# Lilypad_Schematic_1.net
KiCad netlist of a schematic drawn in Altium Designer
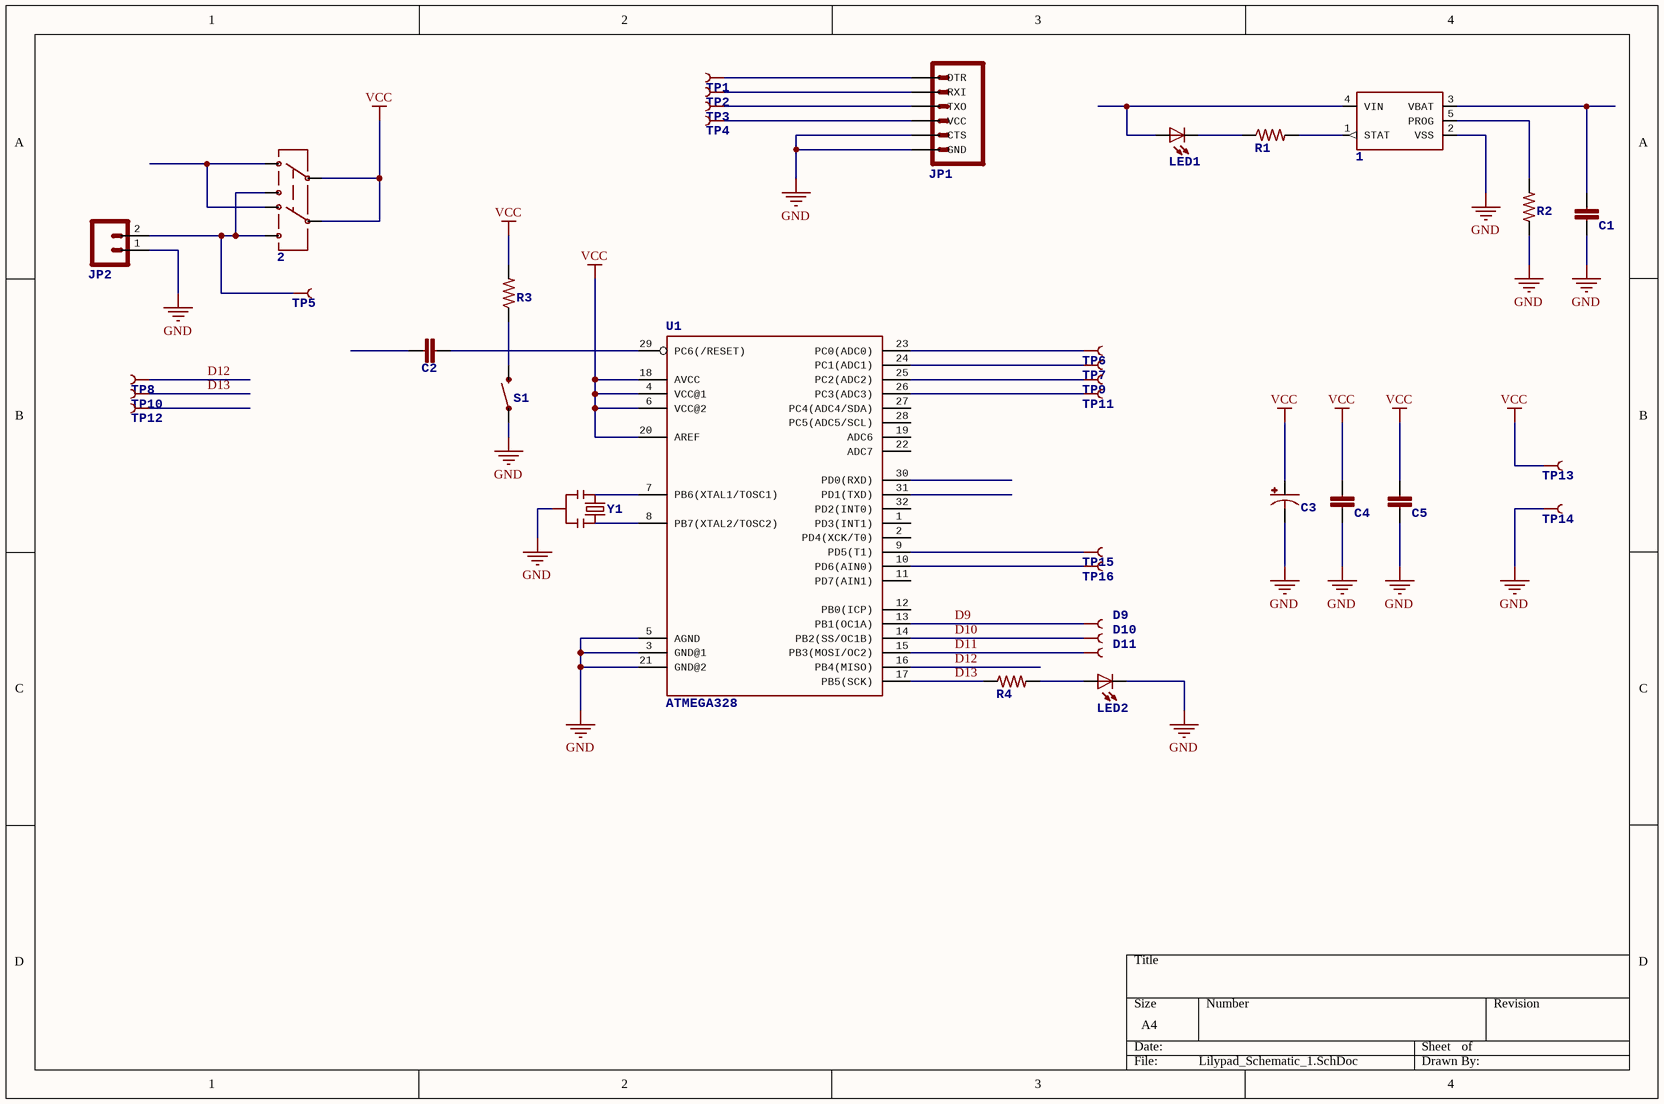
[diagram p0: Lilypad_Schematic_1.SchDoc]

(export (version "E")
  (design (tool "Eeschema 10.0.6"))
  (components
    (comp (ref "1")
      (value "MCP73831")
      (footprint "SOT23-5")
      (libsource (lib "LilyPad Simple v2") (part "MCP73831"))
    )
    (comp (ref "2")
      (value "AYZ0202")
      (footprint "AYZ0202")
      (libsource (lib "LilyPad Simple v2") (part "AYZ0202"))
    )
    (comp (ref "C1") (value "CAP0402-CAP") (footprint "0402-CAP") (libsource (lib "") (part "CAP0402-CAP_1")))
    (comp (ref "C2")
      (value "CAP0402-CAP")
      (footprint "0402-CAP")
      (libsource (lib "LilyPad Simple v2") (part "CAP0402-CAP"))
    )
    (comp (ref "C3")
      (value "CAP_POL3528")
      (footprint "EIA3528")
      (libsource (lib "LilyPad Simple v2") (part "CAP_POL3528"))
    )
    (comp (ref "C4") (value "CAP0402-CAP") (footprint "0402-CAP") (libsource (lib "") (part "CAP0402-CAP_1")))
    (comp (ref "C5") (value "CAP0402-CAP") (footprint "0402-CAP") (libsource (lib "") (part "CAP0402-CAP_1")))
    (comp (ref "D9")
      (value "CONN")
      (footprint "PETAL-LONG-2")
      (libsource (lib "LilyPad Simple v2") (part "CONN"))
    )
    (comp (ref "D10")
      (value "CONN")
      (footprint "PETAL-LONG-2")
      (libsource (lib "LilyPad Simple v2") (part "CONN"))
    )
    (comp (ref "D11")
      (value "CONN")
      (footprint "PETAL-LONG-2")
      (libsource (lib "LilyPad Simple v2") (part "CONN"))
    )
    (comp (ref "JP1")
      (value "ARDUINO_SERIAL_PROGRAMSMD")
      (footprint "1X06-SMD")
      (libsource (lib "LilyPad Simple v2") (part "ARDUINO_SERIAL_PROGRAMSMD"))
    )
    (comp (ref "JP2")
      (value "M02-JST-2MM-SMT")
      (footprint "JST-2-SMD")
      (libsource (lib "LilyPad Simple v2") (part "M02-JST-2MM-SMT"))
    )
    (comp (ref "LED1")
      (value "LED0603")
      (footprint "LED-0603")
      (libsource (lib "LilyPad Simple v2") (part "LED0603"))
    )
    (comp (ref "LED2")
      (value "LED0603")
      (footprint "LED-0603")
      (libsource (lib "LilyPad Simple v2") (part "LED0603"))
    )
    (comp (ref "R1")
      (value "RESISTOR0402-RES")
      (footprint "0402-RES")
      (libsource (lib "LilyPad Simple v2") (part "RESISTOR0402-RES"))
    )
    (comp (ref "R2")
      (value "RESISTOR0402-RES")
      (footprint "0402-RES")
      (libsource (lib "LilyPad Simple v2") (part "RESISTOR0402-RES"))
    )
    (comp (ref "R3")
      (value "RESISTOR0402-RES")
      (footprint "0402-RES")
      (libsource (lib "LilyPad Simple v2") (part "RESISTOR0402-RES"))
    )
    (comp (ref "R4")
      (value "RESISTOR0402-RES")
      (footprint "0402-RES")
      (libsource (lib "LilyPad Simple v2") (part "RESISTOR0402-RES"))
    )
    (comp (ref "S1")
      (value "SWITCH-MOMENTARY-2SMD-2")
      (footprint "TACTILE_SWITCH_SMD-2")
      (libsource (lib "LilyPad Simple v2") (part "SWITCH-MOMENTARY-2SMD-2"))
    )
    (comp (ref "TP1")
      (value "TEST-POINT3X5")
      (footprint "PAD.03X.05")
      (libsource (lib "LilyPad Simple v2") (part "TEST-POINT3X5"))
    )
    (comp (ref "TP2")
      (value "TEST-POINT3X5")
      (footprint "PAD.03X.05")
      (libsource (lib "LilyPad Simple v2") (part "TEST-POINT3X5"))
    )
    (comp (ref "TP3")
      (value "TEST-POINT3X5")
      (footprint "PAD.03X.05")
      (libsource (lib "LilyPad Simple v2") (part "TEST-POINT3X5"))
    )
    (comp (ref "TP4")
      (value "TEST-POINT3X5")
      (footprint "PAD.03X.05")
      (libsource (lib "LilyPad Simple v2") (part "TEST-POINT3X5"))
    )
    (comp (ref "TP5")
      (value "TEST-POINT3X5")
      (footprint "PAD.03X.05")
      (libsource (lib "LilyPad Simple v2") (part "TEST-POINT3X5"))
    )
    (comp (ref "TP6")
      (value "CONN")
      (footprint "PETAL-LONG-2")
      (libsource (lib "LilyPad Simple v2") (part "CONN"))
    )
    (comp (ref "TP7")
      (value "CONN")
      (footprint "PETAL-LONG-2")
      (libsource (lib "LilyPad Simple v2") (part "CONN"))
    )
    (comp (ref "TP8")
      (value "TEST-POINT3X5")
      (footprint "PAD.03X.05")
      (libsource (lib "LilyPad Simple v2") (part "TEST-POINT3X5"))
    )
    (comp (ref "TP9")
      (value "CONN")
      (footprint "PETAL-LONG-2")
      (libsource (lib "LilyPad Simple v2") (part "CONN"))
    )
    (comp (ref "TP10")
      (value "TEST-POINT3X5")
      (footprint "PAD.03X.05")
      (libsource (lib "LilyPad Simple v2") (part "TEST-POINT3X5"))
    )
    (comp (ref "TP11")
      (value "CONN")
      (footprint "PETAL-LONG-2")
      (libsource (lib "LilyPad Simple v2") (part "CONN"))
    )
    (comp (ref "TP12")
      (value "TEST-POINT3X5")
      (footprint "PAD.03X.05")
      (libsource (lib "LilyPad Simple v2") (part "TEST-POINT3X5"))
    )
    (comp (ref "TP13")
      (value "CONN")
      (footprint "PETAL-LONG-2")
      (libsource (lib "LilyPad Simple v2") (part "CONN"))
    )
    (comp (ref "TP14")
      (value "CONN")
      (footprint "PETAL-LONG-2")
      (libsource (lib "LilyPad Simple v2") (part "CONN"))
    )
    (comp (ref "TP15")
      (value "CONN")
      (footprint "PETAL-LONG-2")
      (libsource (lib "LilyPad Simple v2") (part "CONN"))
    )
    (comp (ref "TP16")
      (value "CONN")
      (footprint "PETAL-LONG-2")
      (libsource (lib "LilyPad Simple v2") (part "CONN"))
    )
    (comp (ref "U1")
      (value "ATMEGA328")
      (footprint "TQFP32-08")
      (libsource (lib "LilyPad Simple v2") (part "ATMEGA328"))
    )
    (comp (ref "Y1")
      (value "RESONATORSMD")
      (footprint "RESONATOR-SMD")
      (libsource (lib "LilyPad Simple v2") (part "RESONATORSMD"))
    )
  )
  (nets
    (net (code "1") (name "/D9") (class "Default")
      (node (ref "D9") (pin "1") (pinfunction "1_1") (pintype "passive"))
      (node (ref "U1") (pin "13") (pinfunction "PB1(OC1A)_13") (pintype "passive"))
    )
    (net (code "2") (name "/D10") (class "Default")
      (node (ref "D10") (pin "1") (pinfunction "1_1") (pintype "passive"))
      (node (ref "U1") (pin "14") (pinfunction "PB2(SS/OC1B)_14") (pintype "passive"))
    )
    (net (code "3") (name "/D11") (class "Default")
      (node (ref "D11") (pin "1") (pinfunction "1_1") (pintype "passive"))
      (node (ref "U1") (pin "15") (pinfunction "PB3(MOSI/OC2)_15") (pintype "passive"))
    )
    (net (code "4") (name "/D12") (class "Default")
      (node (ref "TP8") (pin "P$1") (pinfunction "1_P$1") (pintype "passive"))
      (node (ref "U1") (pin "16") (pinfunction "PB4(MISO)_16") (pintype "passive"))
    )
    (net (code "5") (name "/D13") (class "Default")
      (node (ref "R4") (pin "1") (pinfunction "1_1") (pintype "passive"))
      (node (ref "TP10") (pin "P$1") (pinfunction "1_P$1") (pintype "passive"))
      (node (ref "U1") (pin "17") (pinfunction "PB5(SCK)_17") (pintype "passive"))
    )
    (net (code "6") (name "GND") (class "Default")
      (node (ref "1") (pin "2") (pinfunction "VSS_2") (pintype "power_in"))
      (node (ref "C1") (pin "2") (pinfunction "2_2") (pintype "passive"))
      (node (ref "C3") (pin "C") (pinfunction "-_C") (pintype "passive"))
      (node (ref "C4") (pin "2") (pinfunction "2_2") (pintype "passive"))
      (node (ref "C5") (pin "2") (pinfunction "2_2") (pintype "passive"))
      (node (ref "JP1") (pin "5") (pinfunction "CTS_5") (pintype "passive"))
      (node (ref "JP1") (pin "6") (pinfunction "GND_6") (pintype "passive"))
      (node (ref "JP2") (pin "1") (pinfunction "1_1") (pintype "passive"))
      (node (ref "LED2") (pin "C") (pinfunction "C_C") (pintype "passive"))
      (node (ref "R2") (pin "1") (pinfunction "1_1") (pintype "passive"))
      (node (ref "S1") (pin "2") (pinfunction "1_2") (pintype "passive"))
      (node (ref "TP14") (pin "1") (pinfunction "1_1") (pintype "passive"))
      (node (ref "U1") (pin "21") (pinfunction "GND@2_21") (pintype "passive"))
      (node (ref "U1") (pin "3") (pinfunction "GND@1_3") (pintype "passive"))
      (node (ref "U1") (pin "5") (pinfunction "AGND_5") (pintype "passive"))
      (node (ref "Y1") (pin "2") (pinfunction "2_2") (pintype "passive"))
    )
    (net (code "7") (name "Net-(1-PROG)") (class "Default")
      (node (ref "1") (pin "5") (pinfunction "PROG_5") (pintype "passive"))
      (node (ref "R2") (pin "2") (pinfunction "2_2") (pintype "passive"))
    )
    (net (code "8") (name "Net-(1-STAT)") (class "Default")
      (node (ref "1") (pin "1") (pinfunction "STAT_1") (pintype "output"))
      (node (ref "R1") (pin "2") (pinfunction "2_2") (pintype "passive"))
    )
    (net (code "9") (name "Net-(1-VBAT)") (class "Default")
      (node (ref "1") (pin "3") (pinfunction "VBAT_3") (pintype "power_in"))
      (node (ref "C1") (pin "1") (pinfunction "1_1") (pintype "passive"))
    )
    (net (code "10") (name "Net-(1-VIN)") (class "Default")
      (node (ref "1") (pin "4") (pinfunction "VIN_4") (pintype "power_in"))
      (node (ref "LED1") (pin "A") (pinfunction "A_A") (pintype "passive"))
    )
    (net (code "11") (name "Net-(2-1)") (class "Default")
      (node (ref "2") (pin "3") (pinfunction "1_3") (pintype "passive"))
      (node (ref "2") (pin "6") (pinfunction "4_6") (pintype "passive"))
    )
    (net (code "12") (name "Net-(2-3)") (class "Default")
      (node (ref "2") (pin "1") (pinfunction "3_1") (pintype "passive"))
      (node (ref "2") (pin "4") (pinfunction "6_4") (pintype "passive"))
      (node (ref "JP2") (pin "2") (pinfunction "2_2") (pintype "passive"))
      (node (ref "TP5") (pin "P$1") (pinfunction "1_P$1") (pintype "passive"))
    )
    (net (code "13") (name "Net-(JP1-DTR)") (class "Default")
      (node (ref "JP1") (pin "1") (pinfunction "DTR_1") (pintype "passive"))
      (node (ref "TP1") (pin "P$1") (pinfunction "1_P$1") (pintype "passive"))
    )
    (net (code "14") (name "Net-(JP1-RXI)") (class "Default")
      (node (ref "JP1") (pin "2") (pinfunction "RXI_2") (pintype "passive"))
      (node (ref "TP2") (pin "P$1") (pinfunction "1_P$1") (pintype "passive"))
    )
    (net (code "15") (name "Net-(JP1-TXO)") (class "Default")
      (node (ref "JP1") (pin "3") (pinfunction "TXO_3") (pintype "passive"))
      (node (ref "TP3") (pin "P$1") (pinfunction "1_P$1") (pintype "passive"))
    )
    (net (code "16") (name "Net-(JP1-VCC)") (class "Default")
      (node (ref "JP1") (pin "4") (pinfunction "VCC_4") (pintype "passive"))
      (node (ref "TP4") (pin "P$1") (pinfunction "1_P$1") (pintype "passive"))
    )
    (net (code "17") (name "Net-(LED1-PadC)") (class "Default")
      (node (ref "LED1") (pin "C") (pinfunction "C_C") (pintype "passive"))
      (node (ref "R1") (pin "1") (pinfunction "1_1") (pintype "passive"))
    )
    (net (code "18") (name "Net-(LED2-PadA)") (class "Default")
      (node (ref "LED2") (pin "A") (pinfunction "A_A") (pintype "passive"))
      (node (ref "R4") (pin "2") (pinfunction "2_2") (pintype "passive"))
    )
    (net (code "19") (name "Net-(S1-2)") (class "Default")
      (node (ref "R3") (pin "1") (pinfunction "1_1") (pintype "passive"))
      (node (ref "S1") (pin "1") (pinfunction "2_1") (pintype "passive"))
    )
    (net (code "20") (name "Net-(U1-PB6(XTAL1{slash}TOSC1))") (class "Default")
      (node (ref "U1") (pin "7") (pinfunction "PB6(XTAL1/TOSC1)_7") (pintype "passive"))
      (node (ref "Y1") (pin "1") (pinfunction "1_1") (pintype "passive"))
    )
    (net (code "21") (name "Net-(U1-PB7(XTAL2{slash}TOSC2))") (class "Default")
      (node (ref "U1") (pin "8") (pinfunction "PB7(XTAL2/TOSC2)_8") (pintype "passive"))
      (node (ref "Y1") (pin "3") (pinfunction "3_3") (pintype "passive"))
    )
    (net (code "22") (name "Net-(U1-PC0(ADC0))") (class "Default")
      (node (ref "TP6") (pin "1") (pinfunction "1_1") (pintype "passive"))
      (node (ref "U1") (pin "23") (pinfunction "PC0(ADC0)_23") (pintype "passive"))
    )
    (net (code "23") (name "Net-(U1-PC1(ADC1))") (class "Default")
      (node (ref "TP7") (pin "1") (pinfunction "1_1") (pintype "passive"))
      (node (ref "U1") (pin "24") (pinfunction "PC1(ADC1)_24") (pintype "passive"))
    )
    (net (code "24") (name "Net-(U1-PC2(ADC2))") (class "Default")
      (node (ref "TP9") (pin "1") (pinfunction "1_1") (pintype "passive"))
      (node (ref "U1") (pin "25") (pinfunction "PC2(ADC2)_25") (pintype "passive"))
    )
    (net (code "25") (name "Net-(U1-PC3(ADC3))") (class "Default")
      (node (ref "TP11") (pin "1") (pinfunction "1_1") (pintype "passive"))
      (node (ref "U1") (pin "26") (pinfunction "PC3(ADC3)_26") (pintype "passive"))
    )
    (net (code "26") (name "Net-(U1-PC6({slash}RESET))") (class "Default")
      (node (ref "C2") (pin "2") (pinfunction "2_2") (pintype "passive"))
      (node (ref "U1") (pin "29") (pinfunction "PC6(/RESET)_29") (pintype "passive"))
    )
    (net (code "27") (name "Net-(U1-PD5(T1))") (class "Default")
      (node (ref "TP15") (pin "1") (pinfunction "1_1") (pintype "passive"))
      (node (ref "U1") (pin "9") (pinfunction "PD5(T1)_9") (pintype "passive"))
    )
    (net (code "28") (name "Net-(U1-PD6(AIN0))") (class "Default")
      (node (ref "TP16") (pin "1") (pinfunction "1_1") (pintype "passive"))
      (node (ref "U1") (pin "10") (pinfunction "PD6(AIN0)_10") (pintype "passive"))
    )
    (net (code "29") (name "VCC") (class "Default")
      (node (ref "2") (pin "2") (pinfunction "2_2") (pintype "passive"))
      (node (ref "2") (pin "5") (pinfunction "5_5") (pintype "passive"))
      (node (ref "C3") (pin "A") (pinfunction "+_A") (pintype "passive"))
      (node (ref "C4") (pin "1") (pinfunction "1_1") (pintype "passive"))
      (node (ref "C5") (pin "1") (pinfunction "1_1") (pintype "passive"))
      (node (ref "R3") (pin "2") (pinfunction "2_2") (pintype "passive"))
      (node (ref "TP13") (pin "1") (pinfunction "1_1") (pintype "passive"))
      (node (ref "U1") (pin "18") (pinfunction "AVCC_18") (pintype "passive"))
      (node (ref "U1") (pin "20") (pinfunction "AREF_20") (pintype "passive"))
      (node (ref "U1") (pin "4") (pinfunction "VCC@1_4") (pintype "passive"))
      (node (ref "U1") (pin "6") (pinfunction "VCC@2_6") (pintype "passive"))
    )
    (net (code "30") (name "unconnected-(C2-Pad1)") (class "Default")
      (node (ref "C2") (pin "1") (pinfunction "1_1") (pintype "passive"))
    )
    (net (code "31") (name "unconnected-(TP12-1-PadP$1)") (class "Default")
      (node (ref "TP12") (pin "P$1") (pinfunction "1_P$1") (pintype "passive"))
    )
    (net (code "32") (name "unconnected-(U1-ADC6-Pad19)") (class "Default")
      (node (ref "U1") (pin "19") (pinfunction "ADC6_19") (pintype "passive"))
    )
    (net (code "33") (name "unconnected-(U1-ADC7-Pad22)") (class "Default")
      (node (ref "U1") (pin "22") (pinfunction "ADC7_22") (pintype "passive"))
    )
    (net (code "34") (name "unconnected-(U1-PB0(ICP)-Pad12)") (class "Default")
      (node (ref "U1") (pin "12") (pinfunction "PB0(ICP)_12") (pintype "passive"))
    )
    (net (code "35") (name "unconnected-(U1-PC4(ADC4{slash}SDA)-Pad27)") (class "Default")
      (node (ref "U1") (pin "27") (pinfunction "PC4(ADC4/SDA)_27") (pintype "passive"))
    )
    (net (code "36") (name "unconnected-(U1-PC5(ADC5{slash}SCL)-Pad28)") (class "Default")
      (node (ref "U1") (pin "28") (pinfunction "PC5(ADC5/SCL)_28") (pintype "passive"))
    )
    (net (code "37") (name "unconnected-(U1-PD0(RXD)-Pad30)") (class "Default")
      (node (ref "U1") (pin "30") (pinfunction "PD0(RXD)_30") (pintype "passive"))
    )
    (net (code "38") (name "unconnected-(U1-PD1(TXD)-Pad31)") (class "Default")
      (node (ref "U1") (pin "31") (pinfunction "PD1(TXD)_31") (pintype "passive"))
    )
    (net (code "39") (name "unconnected-(U1-PD2(INT0)-Pad32)") (class "Default")
      (node (ref "U1") (pin "32") (pinfunction "PD2(INT0)_32") (pintype "passive"))
    )
    (net (code "40") (name "unconnected-(U1-PD3(INT1)-Pad1)") (class "Default")
      (node (ref "U1") (pin "1") (pinfunction "PD3(INT1)_1") (pintype "passive"))
    )
    (net (code "41") (name "unconnected-(U1-PD4(XCK{slash}T0)-Pad2)") (class "Default")
      (node (ref "U1") (pin "2") (pinfunction "PD4(XCK/T0)_2") (pintype "passive"))
    )
    (net (code "42") (name "unconnected-(U1-PD7(AIN1)-Pad11)") (class "Default")
      (node (ref "U1") (pin "11") (pinfunction "PD7(AIN1)_11") (pintype "passive"))
    )
  )
)
